# Sheet2.net
KiCad netlist of a schematic drawn in Altium Designer
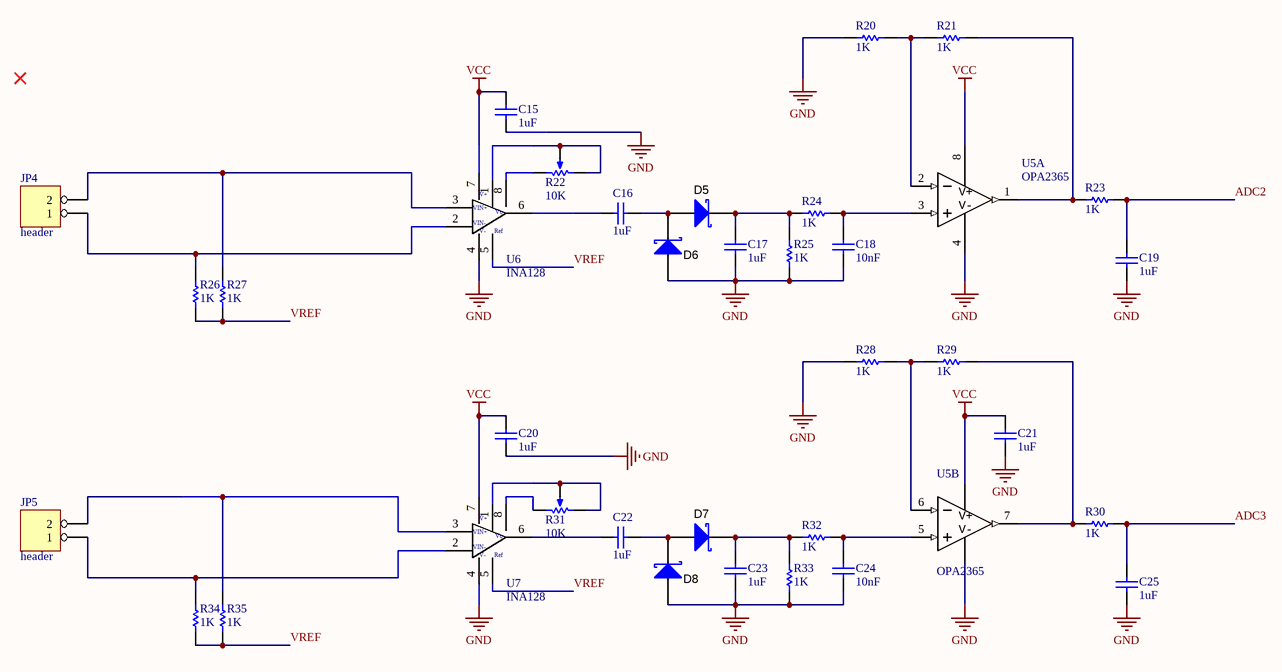
[diagram p0: Sheet2.SchDoc]

(export (version "E")
  (design (tool "Eeschema 10.0.6"))
  (components
    (comp (ref "C15")
      (value "1uF")
      (footprint "0603_C")
      (description "Capacitor")
      (fields (field (name "PUBLISHER") "Altium Limited"))
      (libsource (lib "LY御用集成库") (part "CAP"))
    )
    (comp (ref "C16")
      (value "1uF")
      (footprint "0603_C")
      (description "Capacitor")
      (fields (field (name "PUBLISHER") "Altium Limited"))
      (libsource (lib "LY御用集成库") (part "CAP"))
    )
    (comp (ref "C17")
      (value "1uF")
      (footprint "0603_C")
      (description "Capacitor")
      (fields (field (name "PUBLISHER") "Altium Limited"))
      (libsource (lib "LY御用集成库") (part "CAP"))
    )
    (comp (ref "C18")
      (value "10nF")
      (footprint "0603_C")
      (description "Capacitor")
      (fields (field (name "PUBLISHER") "Altium Limited"))
      (libsource (lib "LY御用集成库") (part "CAP"))
    )
    (comp (ref "C19")
      (value "1uF")
      (footprint "0603_C")
      (description "Capacitor")
      (fields (field (name "PUBLISHER") "Altium Limited"))
      (libsource (lib "LY御用集成库") (part "CAP"))
    )
    (comp (ref "C20")
      (value "1uF")
      (footprint "0603_C")
      (description "Capacitor")
      (fields (field (name "PUBLISHER") "Altium Limited"))
      (libsource (lib "LY御用集成库") (part "CAP"))
    )
    (comp (ref "C21")
      (value "1uF")
      (footprint "0603_C")
      (description "Capacitor")
      (fields (field (name "PUBLISHER") "Altium Limited"))
      (libsource (lib "LY御用集成库") (part "CAP"))
    )
    (comp (ref "C22")
      (value "1uF")
      (footprint "0603_C")
      (description "Capacitor")
      (fields (field (name "PUBLISHER") "Altium Limited"))
      (libsource (lib "LY御用集成库") (part "CAP"))
    )
    (comp (ref "C23")
      (value "1uF")
      (footprint "0603_C")
      (description "Capacitor")
      (fields (field (name "PUBLISHER") "Altium Limited"))
      (libsource (lib "LY御用集成库") (part "CAP"))
    )
    (comp (ref "C24")
      (value "10nF")
      (footprint "0603_C")
      (description "Capacitor")
      (fields (field (name "PUBLISHER") "Altium Limited"))
      (libsource (lib "LY御用集成库") (part "CAP"))
    )
    (comp (ref "C25")
      (value "1uF")
      (footprint "0603_C")
      (description "Capacitor")
      (fields (field (name "PUBLISHER") "Altium Limited"))
      (libsource (lib "LY御用集成库") (part "CAP"))
    )
    (comp (ref "D5")
      (value "Diode, Schottky")
      (footprint "SOD323")
      (description "Diode, Schottky, 40 V, 0.2 A, DO-213AC")
      (fields
        (field (name "MANUFACTURER") "Vishay-Semiconductor")
        (field (name "PARTNUMBER") "LL103A-GS08")
        (field (name "PUBLISHER") "Texas Instruments")
      )
      (libsource (lib "小车") (part "D_Schottky"))
    )
    (comp (ref "D6")
      (value "Diode, Schottky")
      (footprint "SOD323")
      (description "Diode, Schottky, 40 V, 0.2 A, DO-213AC")
      (fields
        (field (name "MANUFACTURER") "Vishay-Semiconductor")
        (field (name "PARTNUMBER") "LL103A-GS08")
        (field (name "PUBLISHER") "Texas Instruments")
      )
      (libsource (lib "小车") (part "D_Schottky"))
    )
    (comp (ref "D7")
      (value "Diode, Schottky")
      (footprint "SOD323")
      (description "Diode, Schottky, 40 V, 0.2 A, DO-213AC")
      (fields
        (field (name "MANUFACTURER") "Vishay-Semiconductor")
        (field (name "PARTNUMBER") "LL103A-GS08")
        (field (name "PUBLISHER") "Texas Instruments")
      )
      (libsource (lib "小车") (part "D_Schottky"))
    )
    (comp (ref "D8")
      (value "Diode, Schottky")
      (footprint "SOD323")
      (description "Diode, Schottky, 40 V, 0.2 A, DO-213AC")
      (fields
        (field (name "MANUFACTURER") "Vishay-Semiconductor")
        (field (name "PARTNUMBER") "LL103A-GS08")
        (field (name "PUBLISHER") "Texas Instruments")
      )
      (libsource (lib "小车") (part "D_Schottky"))
    )
    (comp (ref "JP4")
      (value "header")
      (footprint "header2")
      (libsource (lib "My Footprint") (part "HEADER 2"))
    )
    (comp (ref "JP5")
      (value "header")
      (footprint "header2")
      (libsource (lib "My Footprint") (part "HEADER 2"))
    )
    (comp (ref "R20")
      (value "1K")
      (footprint "R0603")
      (description "Resistor")
      (fields (field (name "PUBLISHER") "Altium Limited"))
      (libsource (lib "LY御用集成库") (part "RES"))
    )
    (comp (ref "R21")
      (value "1K")
      (footprint "R0603")
      (description "Resistor")
      (fields (field (name "PUBLISHER") "Altium Limited"))
      (libsource (lib "LY御用集成库") (part "RES"))
    )
    (comp (ref "R22") (value "10K") (footprint "3224W") (libsource (lib "My Footprint") (part "单联电位器")))
    (comp (ref "R23")
      (value "1K")
      (footprint "R0603")
      (description "Resistor")
      (fields (field (name "PUBLISHER") "Altium Limited"))
      (libsource (lib "LY御用集成库") (part "RES"))
    )
    (comp (ref "R24")
      (value "1K")
      (footprint "R0603")
      (description "Resistor")
      (fields (field (name "PUBLISHER") "Altium Limited"))
      (libsource (lib "LY御用集成库") (part "RES"))
    )
    (comp (ref "R25")
      (value "1K")
      (footprint "R0603")
      (description "Resistor")
      (fields (field (name "PUBLISHER") "Altium Limited"))
      (libsource (lib "LY御用集成库") (part "RES"))
    )
    (comp (ref "R26")
      (value "1K")
      (footprint "R0603")
      (description "Resistor")
      (fields (field (name "PUBLISHER") "Altium Limited"))
      (libsource (lib "LY御用集成库") (part "RES"))
    )
    (comp (ref "R27")
      (value "1K")
      (footprint "R0603")
      (description "Resistor")
      (fields (field (name "PUBLISHER") "Altium Limited"))
      (libsource (lib "LY御用集成库") (part "RES"))
    )
    (comp (ref "R28")
      (value "1K")
      (footprint "R0603")
      (description "Resistor")
      (fields (field (name "PUBLISHER") "Altium Limited"))
      (libsource (lib "LY御用集成库") (part "RES"))
    )
    (comp (ref "R29")
      (value "1K")
      (footprint "R0603")
      (description "Resistor")
      (fields (field (name "PUBLISHER") "Altium Limited"))
      (libsource (lib "LY御用集成库") (part "RES"))
    )
    (comp (ref "R30")
      (value "1K")
      (footprint "R0603")
      (description "Resistor")
      (fields (field (name "PUBLISHER") "Altium Limited"))
      (libsource (lib "LY御用集成库") (part "RES"))
    )
    (comp (ref "R31") (value "10K") (footprint "3224W") (libsource (lib "My Footprint") (part "单联电位器")))
    (comp (ref "R32")
      (value "1K")
      (footprint "R0603")
      (description "Resistor")
      (fields (field (name "PUBLISHER") "Altium Limited"))
      (libsource (lib "LY御用集成库") (part "RES"))
    )
    (comp (ref "R33")
      (value "1K")
      (footprint "R0603")
      (description "Resistor")
      (fields (field (name "PUBLISHER") "Altium Limited"))
      (libsource (lib "LY御用集成库") (part "RES"))
    )
    (comp (ref "R34")
      (value "1K")
      (footprint "R0603")
      (description "Resistor")
      (fields (field (name "PUBLISHER") "Altium Limited"))
      (libsource (lib "LY御用集成库") (part "RES"))
    )
    (comp (ref "R35")
      (value "1K")
      (footprint "R0603")
      (description "Resistor")
      (fields (field (name "PUBLISHER") "Altium Limited"))
      (libsource (lib "LY御用集成库") (part "RES"))
    )
    (comp (ref "U5")
      (value "OPA2365")
      (footprint "SOP8")
      (description "Imported")
      (fields
        (field (name "MANUFACTURER") "Texas Instruments")
        (field (name "MANUFACTURER_PART_NUMBER") "opa2365_d_8")
      )
      (libsource (lib "My Footprint(1)") (part "OPA2365"))
    )
    (comp (ref "U6") (value "INA128") (footprint "SOIC-8") (libsource (lib "Common Device") (part "INA118")))
    (comp (ref "U7") (value "INA128") (footprint "SOIC-8") (libsource (lib "Common Device") (part "INA118")))
  )
  (nets
    (net (code "1") (name "/ADC2") (class "Default")
      (node (ref "C19") (pin "2") (pinfunction "2_2") (pintype "passive"))
      (node (ref "R23") (pin "1") (pinfunction "1_1") (pintype "passive"))
    )
    (net (code "2") (name "/ADC3") (class "Default")
      (node (ref "C25") (pin "2") (pinfunction "2_2") (pintype "passive"))
      (node (ref "R30") (pin "1") (pinfunction "1_1") (pintype "passive"))
    )
    (net (code "3") (name "/VREF") (class "Default")
      (node (ref "R26") (pin "1") (pinfunction "1_1") (pintype "passive"))
      (node (ref "R27") (pin "1") (pinfunction "1_1") (pintype "passive"))
      (node (ref "R34") (pin "1") (pinfunction "1_1") (pintype "passive"))
      (node (ref "R35") (pin "1") (pinfunction "1_1") (pintype "passive"))
      (node (ref "U6") (pin "5") (pinfunction "Ref_5") (pintype "passive"))
      (node (ref "U7") (pin "5") (pinfunction "Ref_5") (pintype "passive"))
    )
    (net (code "4") (name "GND") (class "Default")
      (node (ref "C15") (pin "1") (pinfunction "1_1") (pintype "passive"))
      (node (ref "C17") (pin "1") (pinfunction "1_1") (pintype "passive"))
      (node (ref "C18") (pin "1") (pinfunction "1_1") (pintype "passive"))
      (node (ref "C19") (pin "1") (pinfunction "1_1") (pintype "passive"))
      (node (ref "C20") (pin "1") (pinfunction "1_1") (pintype "passive"))
      (node (ref "C21") (pin "1") (pinfunction "1_1") (pintype "passive"))
      (node (ref "C23") (pin "1") (pinfunction "1_1") (pintype "passive"))
      (node (ref "C24") (pin "1") (pinfunction "1_1") (pintype "passive"))
      (node (ref "C25") (pin "1") (pinfunction "1_1") (pintype "passive"))
      (node (ref "D6") (pin "2") (pinfunction "A_2") (pintype "passive"))
      (node (ref "D8") (pin "2") (pinfunction "A_2") (pintype "passive"))
      (node (ref "R20") (pin "2") (pinfunction "2_2") (pintype "passive"))
      (node (ref "R25") (pin "1") (pinfunction "1_1") (pintype "passive"))
      (node (ref "R28") (pin "2") (pinfunction "2_2") (pintype "passive"))
      (node (ref "R33") (pin "1") (pinfunction "1_1") (pintype "passive"))
      (node (ref "U5") (pin "4") (pinfunction "V-_4") (pintype "power_in"))
      (node (ref "U6") (pin "4") (pinfunction "V-_4") (pintype "passive"))
      (node (ref "U7") (pin "4") (pinfunction "V-_4") (pintype "passive"))
    )
    (net (code "5") (name "Net-(D5-A)") (class "Default")
      (node (ref "C16") (pin "1") (pinfunction "1_1") (pintype "passive"))
      (node (ref "D5") (pin "2") (pinfunction "A_2") (pintype "passive"))
      (node (ref "D6") (pin "1") (pinfunction "K_1") (pintype "passive"))
    )
    (net (code "6") (name "Net-(D5-K)") (class "Default")
      (node (ref "C17") (pin "2") (pinfunction "2_2") (pintype "passive"))
      (node (ref "D5") (pin "1") (pinfunction "K_1") (pintype "passive"))
      (node (ref "R24") (pin "2") (pinfunction "2_2") (pintype "passive"))
      (node (ref "R25") (pin "2") (pinfunction "2_2") (pintype "passive"))
    )
    (net (code "7") (name "Net-(D7-A)") (class "Default")
      (node (ref "C22") (pin "1") (pinfunction "1_1") (pintype "passive"))
      (node (ref "D7") (pin "2") (pinfunction "A_2") (pintype "passive"))
      (node (ref "D8") (pin "1") (pinfunction "K_1") (pintype "passive"))
    )
    (net (code "8") (name "Net-(D7-K)") (class "Default")
      (node (ref "C23") (pin "2") (pinfunction "2_2") (pintype "passive"))
      (node (ref "D7") (pin "1") (pinfunction "K_1") (pintype "passive"))
      (node (ref "R32") (pin "2") (pinfunction "2_2") (pintype "passive"))
      (node (ref "R33") (pin "2") (pinfunction "2_2") (pintype "passive"))
    )
    (net (code "9") (name "Net-(R22-BOT)") (class "Default")
      (node (ref "R22") (pin "1") (pinfunction "BOT_1") (pintype "passive"))
      (node (ref "R22") (pin "2") (pinfunction "TAP_2") (pintype "passive"))
      (node (ref "U6") (pin "1") (pinfunction "0_1") (pintype "passive"))
    )
    (net (code "10") (name "Net-(R22-TOP)") (class "Default")
      (node (ref "R22") (pin "3") (pinfunction "TOP_3") (pintype "passive"))
      (node (ref "U6") (pin "8") (pinfunction "8_8") (pintype "passive"))
    )
    (net (code "11") (name "Net-(R31-BOT)") (class "Default")
      (node (ref "R31") (pin "1") (pinfunction "BOT_1") (pintype "passive"))
      (node (ref "R31") (pin "2") (pinfunction "TAP_2") (pintype "passive"))
      (node (ref "U7") (pin "1") (pinfunction "0_1") (pintype "passive"))
    )
    (net (code "12") (name "Net-(R31-TOP)") (class "Default")
      (node (ref "R31") (pin "3") (pinfunction "TOP_3") (pintype "passive"))
      (node (ref "U7") (pin "8") (pinfunction "8_8") (pintype "passive"))
    )
    (net (code "13") (name "Net-(U5A-1IN+)") (class "Default")
      (node (ref "C18") (pin "2") (pinfunction "2_2") (pintype "passive"))
      (node (ref "R24") (pin "1") (pinfunction "1_1") (pintype "passive"))
      (node (ref "U5") (pin "3") (pinfunction "1IN+_3") (pintype "input"))
    )
    (net (code "14") (name "Net-(U5A-1IN-)") (class "Default")
      (node (ref "R20") (pin "1") (pinfunction "1_1") (pintype "passive"))
      (node (ref "R21") (pin "2") (pinfunction "2_2") (pintype "passive"))
      (node (ref "U5") (pin "2") (pinfunction "1IN-_2") (pintype "input"))
    )
    (net (code "15") (name "Net-(U5A-1OUT)") (class "Default")
      (node (ref "R21") (pin "1") (pinfunction "1_1") (pintype "passive"))
      (node (ref "R23") (pin "2") (pinfunction "2_2") (pintype "passive"))
      (node (ref "U5") (pin "1") (pinfunction "1OUT_1") (pintype "output"))
    )
    (net (code "16") (name "Net-(U5B-2IN+)") (class "Default")
      (node (ref "C24") (pin "2") (pinfunction "2_2") (pintype "passive"))
      (node (ref "R32") (pin "1") (pinfunction "1_1") (pintype "passive"))
      (node (ref "U5") (pin "5") (pinfunction "2IN+_5") (pintype "input"))
    )
    (net (code "17") (name "Net-(U5B-2IN-)") (class "Default")
      (node (ref "R28") (pin "1") (pinfunction "1_1") (pintype "passive"))
      (node (ref "R29") (pin "2") (pinfunction "2_2") (pintype "passive"))
      (node (ref "U5") (pin "6") (pinfunction "2IN-_6") (pintype "input"))
    )
    (net (code "18") (name "Net-(U5B-2OUT)") (class "Default")
      (node (ref "R29") (pin "1") (pinfunction "1_1") (pintype "passive"))
      (node (ref "R30") (pin "2") (pinfunction "2_2") (pintype "passive"))
      (node (ref "U5") (pin "7") (pinfunction "2OUT_7") (pintype "output"))
    )
    (net (code "19") (name "Net-(U6-VIN+)") (class "Default")
      (node (ref "JP4") (pin "2") (pinfunction "2_2") (pintype "passive"))
      (node (ref "R27") (pin "2") (pinfunction "2_2") (pintype "passive"))
      (node (ref "U6") (pin "3") (pinfunction "VIN+_3") (pintype "passive"))
    )
    (net (code "20") (name "Net-(U6-VIN-)") (class "Default")
      (node (ref "JP4") (pin "1") (pinfunction "1_1") (pintype "passive"))
      (node (ref "R26") (pin "2") (pinfunction "2_2") (pintype "passive"))
      (node (ref "U6") (pin "2") (pinfunction "VIN-_2") (pintype "passive"))
    )
    (net (code "21") (name "Net-(U6-Vo)") (class "Default")
      (node (ref "C16") (pin "2") (pinfunction "2_2") (pintype "passive"))
      (node (ref "U6") (pin "6") (pinfunction "Vo_6") (pintype "passive"))
    )
    (net (code "22") (name "Net-(U7-VIN+)") (class "Default")
      (node (ref "JP5") (pin "2") (pinfunction "2_2") (pintype "passive"))
      (node (ref "R35") (pin "2") (pinfunction "2_2") (pintype "passive"))
      (node (ref "U7") (pin "3") (pinfunction "VIN+_3") (pintype "passive"))
    )
    (net (code "23") (name "Net-(U7-VIN-)") (class "Default")
      (node (ref "JP5") (pin "1") (pinfunction "1_1") (pintype "passive"))
      (node (ref "R34") (pin "2") (pinfunction "2_2") (pintype "passive"))
      (node (ref "U7") (pin "2") (pinfunction "VIN-_2") (pintype "passive"))
    )
    (net (code "24") (name "Net-(U7-Vo)") (class "Default")
      (node (ref "C22") (pin "2") (pinfunction "2_2") (pintype "passive"))
      (node (ref "U7") (pin "6") (pinfunction "Vo_6") (pintype "passive"))
    )
    (net (code "25") (name "VCC") (class "Default")
      (node (ref "C15") (pin "2") (pinfunction "2_2") (pintype "passive"))
      (node (ref "C20") (pin "2") (pinfunction "2_2") (pintype "passive"))
      (node (ref "C21") (pin "2") (pinfunction "2_2") (pintype "passive"))
      (node (ref "U5") (pin "8") (pinfunction "V+_8") (pintype "power_in"))
      (node (ref "U6") (pin "7") (pinfunction "V+_7") (pintype "passive"))
      (node (ref "U7") (pin "7") (pinfunction "V+_7") (pintype "passive"))
    )
  )
)
